# speaker.net
KiCad netlist of a schematic drawn in Altium Designer
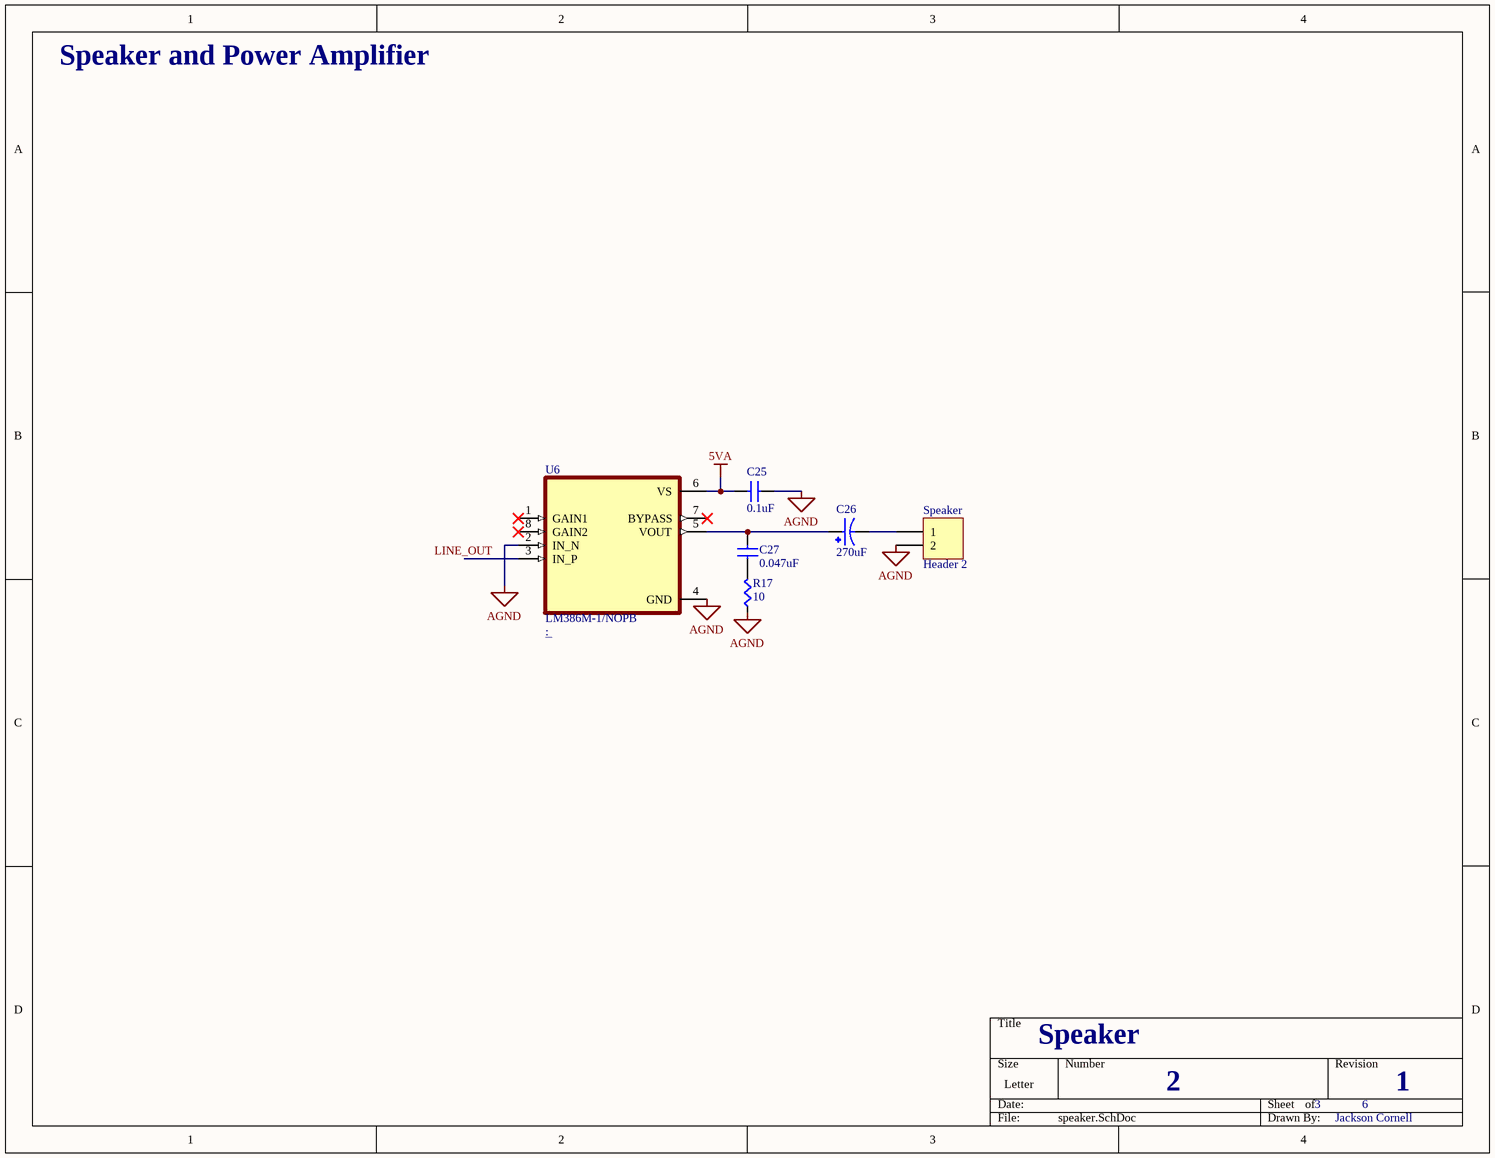
[diagram p0: speaker.SchDoc]

(export (version "E")
  (design (tool "Eeschema 10.0.6"))
  (components
    (comp (ref "C25")
      (value "0.1uF")
      (footprint "CAPC0805")
      (fields (field (name "Comment") "Cap"))
      (libsource (lib "Passives") (part "Cap"))
    )
    (comp (ref "C26")
      (value "270uF")
      (footprint "CAPPRD500W50D500H1100")
      (description "Aluminum Electrolytic Capacitors, 220uF, 6.3V, -40 to 105C")
      (fields (field (name "MF") "Panasonic") (field (name "MP") "EEUFS0J221B"))
      (libsource (lib "EEUFS0J221B") (part "EEUFS0J221B"))
    )
    (comp (ref "C27")
      (value "0.047uF")
      (footprint "CAPC0805")
      (fields (field (name "Comment") "Cap"))
      (libsource (lib "Passives") (part "Cap"))
    )
    (comp (ref "R17")
      (value "10")
      (footprint "RES0805")
      (fields (field (name "Comment") "Res"))
      (libsource (lib "Passives") (part "Res"))
    )
    (comp (ref "Speaker")
      (value "Header 2")
      (footprint "HDR1X2")
      (description "Header, 2-Pin")
      (fields (field (name "PUBLISHER") "Altium Limited"))
      (libsource (lib "Miscellaneous Connectors") (part "Header 2"))
    )
    (comp (ref "U6")
      (value "LM386M-1/NOPB")
      (footprint "SOP65P490X110-8N")
      (description "Wide Input Voltage Low Power Audio Amplifier with Internal Gain")
      (fields (field (name "MP") "LM386M-1") (field (name "MF") "Texas Instruments"))
      (libsource (lib "LM386M-1_NOPB") (part "LM386M-1/NOPB"))
    )
  )
  (nets
    (net (code "1") (name "/LINE_OUT") (class "Default")
      (node (ref "U6") (pin "3") (pinfunction "IN_P_3") (pintype "input"))
    )
    (net (code "2") (name "5VA") (class "Default")
      (node (ref "C25") (pin "2") (pinfunction "B_2") (pintype "passive"))
      (node (ref "U6") (pin "6") (pinfunction "VS_6") (pintype "power_in"))
    )
    (net (code "3") (name "AGND") (class "Default")
      (node (ref "C25") (pin "1") (pinfunction "A_1") (pintype "passive"))
      (node (ref "R17") (pin "2") (pinfunction "B_2") (pintype "passive"))
      (node (ref "Speaker") (pin "2") (pinfunction "2_2") (pintype "passive"))
      (node (ref "U6") (pin "2") (pinfunction "IN_N_2") (pintype "input"))
      (node (ref "U6") (pin "4") (pinfunction "GND_4") (pintype "power_in"))
    )
    (net (code "4") (name "Net-(C26-PadN)") (class "Default")
      (node (ref "C26") (pin "N") (pinfunction "N_N") (pintype "passive"))
      (node (ref "Speaker") (pin "1") (pinfunction "1_1") (pintype "passive"))
    )
    (net (code "5") (name "Net-(C27-A)") (class "Default")
      (node (ref "C26") (pin "P") (pinfunction "P_P") (pintype "passive"))
      (node (ref "C27") (pin "1") (pinfunction "A_1") (pintype "passive"))
      (node (ref "U6") (pin "5") (pinfunction "VOUT_5") (pintype "output"))
    )
    (net (code "6") (name "Net-(C27-B)") (class "Default")
      (node (ref "C27") (pin "2") (pinfunction "B_2") (pintype "passive"))
      (node (ref "R17") (pin "1") (pinfunction "A_1") (pintype "passive"))
    )
    (net (code "7") (name "unconnected-(U6-BYPASS-Pad7)") (class "Default")
      (node (ref "U6") (pin "7") (pinfunction "BYPASS_7") (pintype "output+no_connect"))
    )
    (net (code "8") (name "unconnected-(U6-GAIN1-Pad1)") (class "Default")
      (node (ref "U6") (pin "1") (pinfunction "GAIN1_1") (pintype "input+no_connect"))
    )
    (net (code "9") (name "unconnected-(U6-GAIN2-Pad8)") (class "Default")
      (node (ref "U6") (pin "8") (pinfunction "GAIN2_8") (pintype "input+no_connect"))
    )
  )
)
